# digital-isolator-3in-1out-power.net
KiCad netlist of a schematic drawn in Altium Designer
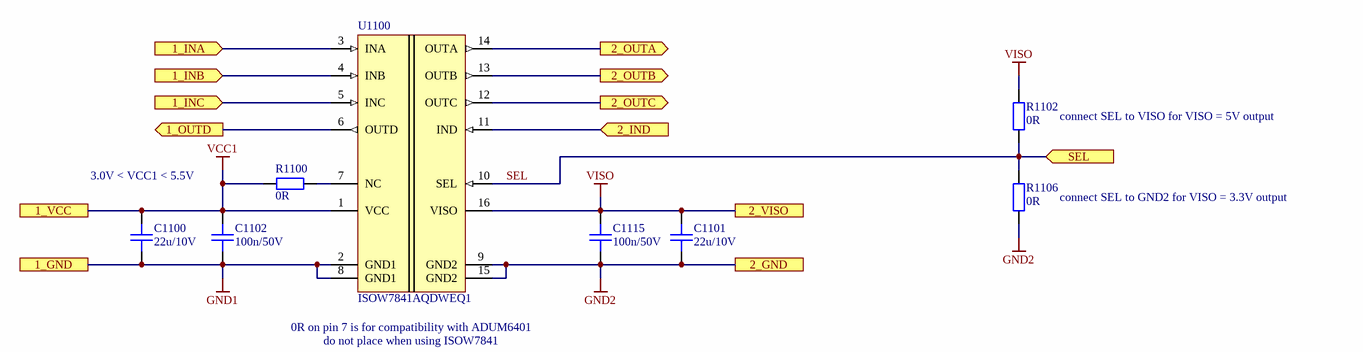
[diagram p0: digital-isolator-3in-1out-power.SchDoc]

(export (version "E")
  (design (tool "Eeschema 10.0.6"))
  (components
    (comp (ref "C1100")
      (value "22u/10V")
      (footprint "CAPC3216X18N")
      (description "MLCC")
      (fields (field (name "PART NUMBER") "gen_C_ceramic_22u_10V_X7R_1206"))
      (libsource (lib "OE750") (part "C"))
    )
    (comp (ref "C1101")
      (value "22u/10V")
      (footprint "CAPC3216X18N")
      (description "MLCC")
      (fields (field (name "PART NUMBER") "gen_C_ceramic_22u_10V_X7R_1206"))
      (libsource (lib "OE750") (part "C"))
    )
    (comp (ref "C1102")
      (value "100n/50V")
      (footprint "CAPC1005X06N")
      (description "MLCC")
      (fields (field (name "PART NUMBER") "gen_C_ceramic_100n_50V_X7R_0402"))
      (libsource (lib "OE750") (part "C"))
    )
    (comp (ref "C1115")
      (value "100n/50V")
      (footprint "CAPC1005X06N")
      (description "MLCC")
      (fields (field (name "PART NUMBER") "gen_C_ceramic_100n_50V_X7R_0402"))
      (libsource (lib "OE750") (part "C"))
    )
    (comp (ref "R1100")
      (value "0R")
      (footprint "RESC1005X04N")
      (description "SMD Resistor 0R 0402")
      (fields (field (name "PART NUMBER") "gen_R_0R_0402") (field (name "POWER") "0.063W"))
      (libsource (lib "OE750") (part "R"))
    )
    (comp (ref "R1102")
      (value "0R")
      (footprint "RESC1005X04N")
      (description "SMD Resistor 0R 0402")
      (fields (field (name "PART NUMBER") "gen_R_0R_0402") (field (name "POWER") "0.063W"))
      (libsource (lib "OE750") (part "R"))
    )
    (comp (ref "R1106")
      (value "0R")
      (footprint "RESC1005X04N")
      (description "SMD Resistor 0R 0402")
      (fields (field (name "PART NUMBER") "gen_R_0R_0402") (field (name "POWER") "0.063W"))
      (libsource (lib "OE750") (part "R"))
    )
    (comp (ref "U1100")
      (value "ISOW7841AQDWEQ1")
      (footprint "TI_DWE0016A")
      (fields (field (name "MANUFACTURER") "Texas Instruments"))
      (libsource (lib "OE750") (part "ISOW7841A"))
    )
  )
  (nets
    (net (code "1") (name "/1_INA") (class "Default")
      (node (ref "U1100") (pin "3") (pinfunction "INA_3") (pintype "input"))
    )
    (net (code "2") (name "/1_INB") (class "Default")
      (node (ref "U1100") (pin "4") (pinfunction "INB_4") (pintype "input"))
    )
    (net (code "3") (name "/1_INC") (class "Default")
      (node (ref "U1100") (pin "5") (pinfunction "INC_5") (pintype "input"))
    )
    (net (code "4") (name "/1_OUTD") (class "Default")
      (node (ref "U1100") (pin "6") (pinfunction "OUTD_6") (pintype "output"))
    )
    (net (code "5") (name "/2_IND") (class "Default")
      (node (ref "U1100") (pin "11") (pinfunction "IND_11") (pintype "input"))
    )
    (net (code "6") (name "/2_OUTA") (class "Default")
      (node (ref "U1100") (pin "14") (pinfunction "OUTA_14") (pintype "output"))
    )
    (net (code "7") (name "/2_OUTB") (class "Default")
      (node (ref "U1100") (pin "13") (pinfunction "OUTB_13") (pintype "output"))
    )
    (net (code "8") (name "/2_OUTC") (class "Default")
      (node (ref "U1100") (pin "12") (pinfunction "OUTC_12") (pintype "output"))
    )
    (net (code "9") (name "/SEL") (class "Default")
      (node (ref "R1102") (pin "1") (pinfunction "1_1") (pintype "passive"))
      (node (ref "R1106") (pin "2") (pinfunction "2_2") (pintype "passive"))
      (node (ref "U1100") (pin "10") (pinfunction "SEL_10") (pintype "input"))
    )
    (net (code "10") (name "GND1") (class "Default")
      (node (ref "C1100") (pin "1") (pinfunction "1_1") (pintype "passive"))
      (node (ref "C1102") (pin "1") (pinfunction "1_1") (pintype "passive"))
      (node (ref "U1100") (pin "2") (pinfunction "GND1_2") (pintype "power_in"))
      (node (ref "U1100") (pin "8") (pinfunction "GND1_8") (pintype "power_in"))
    )
    (net (code "11") (name "GND2") (class "Default")
      (node (ref "C1101") (pin "1") (pinfunction "1_1") (pintype "passive"))
      (node (ref "C1115") (pin "1") (pinfunction "1_1") (pintype "passive"))
      (node (ref "R1106") (pin "1") (pinfunction "1_1") (pintype "passive"))
      (node (ref "U1100") (pin "15") (pinfunction "GND2_15") (pintype "power_in"))
      (node (ref "U1100") (pin "9") (pinfunction "GND2_9") (pintype "power_in"))
    )
    (net (code "12") (name "Net-(U1100-NC)") (class "Default")
      (node (ref "R1100") (pin "1") (pinfunction "1_1") (pintype "passive"))
      (node (ref "U1100") (pin "7") (pinfunction "NC_7") (pintype "passive"))
    )
    (net (code "13") (name "VCC1") (class "Default")
      (node (ref "C1100") (pin "2") (pinfunction "2_2") (pintype "passive"))
      (node (ref "C1102") (pin "2") (pinfunction "2_2") (pintype "passive"))
      (node (ref "R1100") (pin "2") (pinfunction "2_2") (pintype "passive"))
      (node (ref "U1100") (pin "1") (pinfunction "VCC_1") (pintype "power_in"))
    )
    (net (code "14") (name "VISO") (class "Default")
      (node (ref "C1101") (pin "2") (pinfunction "2_2") (pintype "passive"))
      (node (ref "C1115") (pin "2") (pinfunction "2_2") (pintype "passive"))
      (node (ref "R1102") (pin "2") (pinfunction "2_2") (pintype "passive"))
      (node (ref "U1100") (pin "16") (pinfunction "VISO_16") (pintype "power_in"))
    )
  )
)
